# Isolated_MCU_Power_Supply.net
KiCad netlist of a schematic drawn in Altium Designer
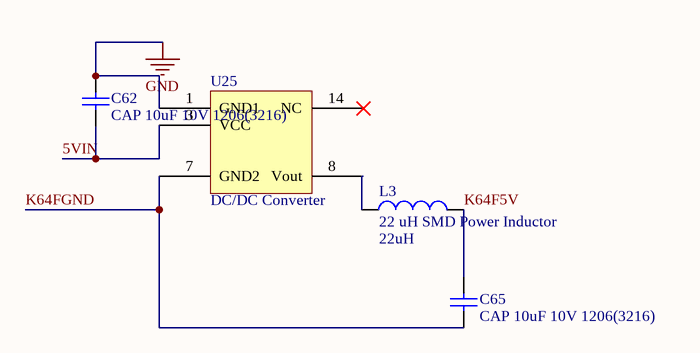
[diagram p0: Isolated MCU Power Supply.SchDoc]

(export (version "E")
  (design (tool "Eeschema 10.0.6"))
  (components
    (comp (ref "C62")
      (value "CAP 10uF 10V 1206(3216)")
      (footprint "CAPC1206(3216)130_L")
      (description "CAP 10uF 10V -20% to +80% 1206 (3216 Metric) Thickness 1.3mm SMD")
      (fields (field (name "TOLERANCE") "-20% to +80%"))
      (libsource (lib "Altium Content Vault") (part "CAP"))
    )
    (comp (ref "C65")
      (value "CAP 10uF 10V 1206(3216)")
      (footprint "CAPC1206(3216)130_L")
      (description "CAP 10uF 10V -20% to +80% 1206 (3216 Metric) Thickness 1.3mm SMD")
      (fields (field (name "TOLERANCE") "-20% to +80%"))
      (libsource (lib "Altium Content Vault") (part "CAP"))
    )
    (comp (ref "L3")
      (value "22 uH SMD Power Inductor")
      (footprint "MURATA PS 8200 Series")
      (description "22 uH SMD Power Inductor, 0.32A RMS, Unshielded, 822 Series, MURATA Power Solutions")
      (fields (field (name "ALTIUM_VALUE") "22uH") (field (name "PUBLISHER") "Adrien Rapeaux"))
      (libsource (lib "ar5113_Altium_Library") (part "MURATA PS 82223C"))
    )
    (comp (ref "U25")
      (value "DC/DC Converter")
      (footprint "MURATA PS NXE2")
      (description "5V-5V Isolated DC/DC Converter, 2W, 12.7 mm x 10.41 mm x 4.41 mm")
      (libsource (lib "ar5113_Altium_Library") (part "MURATA PS NXE2"))
    )
  )
  (nets
    (net (code "1") (name "/5VIN") (class "Default")
      (node (ref "C62") (pin "2") (pinfunction "2_2") (pintype "passive"))
      (node (ref "U25") (pin "3") (pinfunction "VCC_3") (pintype "passive"))
    )
    (net (code "2") (name "/K64F5V") (class "Default")
      (node (ref "C65") (pin "1") (pinfunction "1_1") (pintype "passive"))
      (node (ref "L3") (pin "2") (pinfunction "2_2") (pintype "passive"))
    )
    (net (code "3") (name "/K64FGND") (class "Default")
      (node (ref "C65") (pin "2") (pinfunction "2_2") (pintype "passive"))
      (node (ref "U25") (pin "7") (pinfunction "GND2_7") (pintype "passive"))
    )
    (net (code "4") (name "GND") (class "Default")
      (node (ref "C62") (pin "1") (pinfunction "1_1") (pintype "passive"))
      (node (ref "U25") (pin "1") (pinfunction "GND1_1") (pintype "passive"))
    )
    (net (code "5") (name "Net-(U25-Vout)") (class "Default")
      (node (ref "L3") (pin "1") (pinfunction "1_1") (pintype "passive"))
      (node (ref "U25") (pin "8") (pinfunction "Vout_8") (pintype "passive"))
    )
    (net (code "6") (name "unconnected-(U25-NC-Pad14)") (class "Default")
      (node (ref "U25") (pin "14") (pinfunction "NC_14") (pintype "passive+no_connect"))
    )
  )
)
